# bikelight.net
KiCad netlist of a schematic drawn in Altium Designer
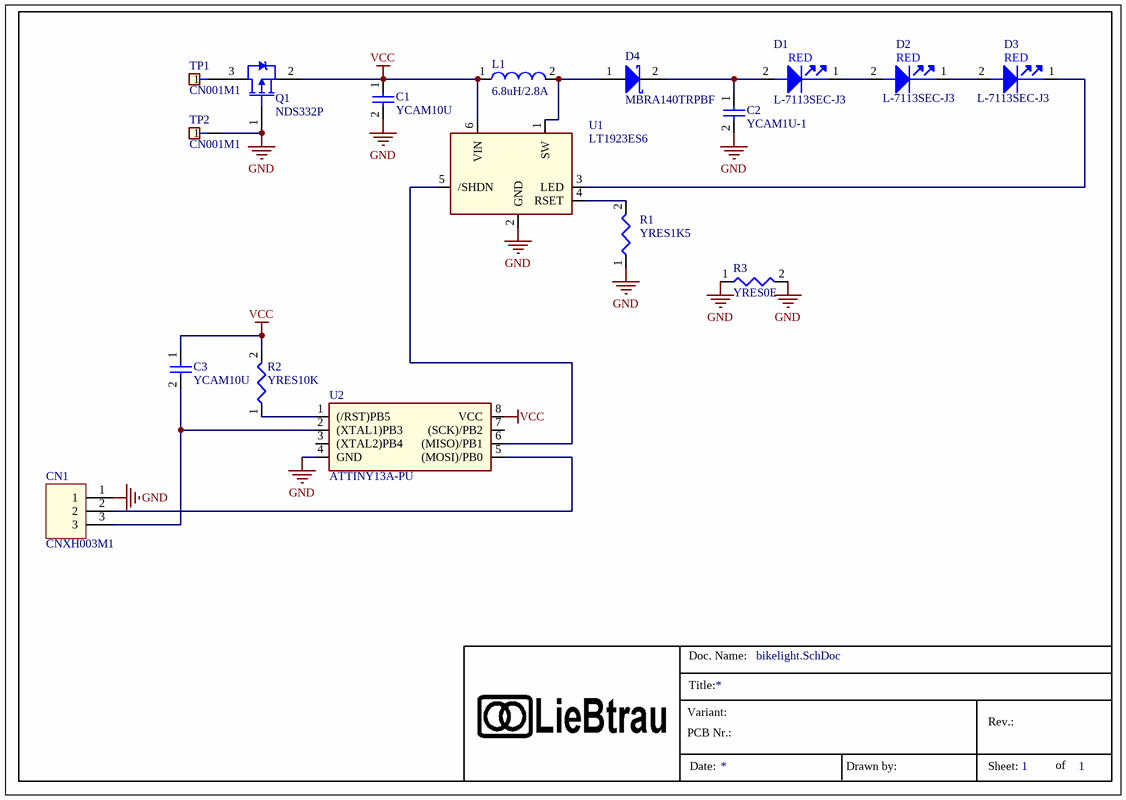
[diagram p0: bikelight.SchDoc]

(export (version "E")
  (design (tool "Eeschema 10.0.6"))
  (components
    (comp (ref "C1") (value "YCAM10U") (footprint "CA_1206") (libsource (lib "Testing") (part "CA_NONPOL")))
    (comp (ref "C2")
      (value "YCAM1U-1")
      (footprint "CA_0805")
      (fields (field (name "MANUFACTURER") "Murata"))
      (libsource (lib "Testing") (part "CA_NONPOL"))
    )
    (comp (ref "C3") (value "YCAM10U") (footprint "CA_1206") (libsource (lib "Testing") (part "CA_NONPOL")))
    (comp (ref "CN1")
      (value "CNXH003M1")
      (footprint "CN_B3B-XH-A")
      (fields (field (name "MANUFACTURER") "JST"))
      (libsource (lib "Testing") (part "CN_3P"))
    )
    (comp (ref "D1")
      (value "L-7113SEC-J3")
      (footprint "DI_LED_5MM")
      (fields (field (name "MANUFACTURER") "Kingbright"))
      (libsource (lib "Testing") (part "DI_LED_RED_2"))
    )
    (comp (ref "D2")
      (value "L-7113SEC-J3")
      (footprint "DI_LED_5MM")
      (fields (field (name "MANUFACTURER") "Kingbright"))
      (libsource (lib "Testing") (part "DI_LED_RED_2"))
    )
    (comp (ref "D3")
      (value "L-7113SEC-J3")
      (footprint "DI_LED_5MM")
      (fields (field (name "MANUFACTURER") "Kingbright"))
      (libsource (lib "Testing") (part "DI_LED_RED_2"))
    )
    (comp (ref "D4")
      (value "MBRA140TRPBF")
      (footprint "DI_DO-214AC")
      (fields (field (name "MANUFACTURER") "Vishay"))
      (libsource (lib "Testing") (part "DI_SCHOTTKY"))
    )
    (comp (ref "L1")
      (value "6.8uH/2.8A")
      (footprint "CL_VISHAY_IHLP-2525CZ-01")
      (fields (field (name "PART NUMBER") "LQH6PPN6R8M43L") (field (name "MANUFACTURER") "Murata"))
      (libsource (lib "Testing") (part "CL_COIL"))
    )
    (comp (ref "Q1")
      (value "NDS332P")
      (footprint "SC_SOT23")
      (fields (field (name "MANUFACTURER") "Fairchild Semiconductor"))
      (libsource (lib "Testing") (part "TR_PMOS"))
    )
    (comp (ref "R1")
      (value "YRES1K5")
      (footprint "RE_1206")
      (description "Resistor")
      (fields (field (name "MANUFACTURER") "Panasonic"))
      (libsource (lib "Testing") (part "RE_RES"))
    )
    (comp (ref "R2")
      (value "YRES10K")
      (footprint "RE_1206")
      (description "Resistor")
      (fields (field (name "MANUFACTURER") "Vishay Draloric"))
      (libsource (lib "Testing") (part "RE_RES"))
    )
    (comp (ref "R3")
      (value "YRES0E")
      (footprint "RE_1206")
      (description "Resistor")
      (fields (field (name "MANUFACTURER") "Vishay Draloric"))
      (libsource (lib "Testing") (part "RE_RES"))
    )
    (comp (ref "TP1")
      (value "CN001M1")
      (footprint "CN_TP_TH_1.3mm")
      (libsource (lib "Testing") (part "CN_TESTPIN"))
    )
    (comp (ref "TP2")
      (value "CN001M1")
      (footprint "CN_TP_TH_1.3mm")
      (libsource (lib "Testing") (part "CN_TESTPIN"))
    )
    (comp (ref "U1")
      (value "LT1923ES6")
      (footprint "SC_SOT23-6")
      (fields (field (name "PART NUMBER") "LT1932ES6") (field (name "MANUFACTURER") "Linear Technology"))
      (libsource (lib "Testing") (part "IC_LT1932"))
    )
    (comp (ref "U2")
      (value "ATTINY13A-PU")
      (footprint "SC_PDIP8")
      (fields (field (name "MANUFACTURER") "Atmel"))
      (libsource (lib "Testing") (part "IC_ATTINY13"))
    )
  )
  (nets
    (net (code "1") (name "GND") (class "Default")
      (node (ref "C1") (pin "2") (pinfunction "2_2") (pintype "passive"))
      (node (ref "C2") (pin "2") (pinfunction "2_2") (pintype "passive"))
      (node (ref "CN1") (pin "1") (pinfunction "1_1") (pintype "passive"))
      (node (ref "Q1") (pin "1") (pinfunction "G_1") (pintype "passive"))
      (node (ref "R1") (pin "1") (pinfunction "1_1") (pintype "passive"))
      (node (ref "R3") (pin "1") (pinfunction "1_1") (pintype "passive"))
      (node (ref "R3") (pin "2") (pinfunction "2_2") (pintype "passive"))
      (node (ref "TP2") (pin "1") (pinfunction "1_1") (pintype "passive"))
      (node (ref "U1") (pin "2") (pinfunction "GND_2") (pintype "passive"))
      (node (ref "U2") (pin "4") (pinfunction "GND_4") (pintype "passive"))
    )
    (net (code "2") (name "Net-(D1-A)") (class "Default")
      (node (ref "D1") (pin "1") (pinfunction "A_1") (pintype "passive"))
      (node (ref "D2") (pin "2") (pinfunction "C_2") (pintype "passive"))
    )
    (net (code "3") (name "Net-(D1-C)") (class "Default")
      (node (ref "C2") (pin "1") (pinfunction "1_1") (pintype "passive"))
      (node (ref "D1") (pin "2") (pinfunction "C_2") (pintype "passive"))
      (node (ref "D4") (pin "2") (pinfunction "K_2") (pintype "passive"))
    )
    (net (code "4") (name "Net-(D2-A)") (class "Default")
      (node (ref "D2") (pin "1") (pinfunction "A_1") (pintype "passive"))
      (node (ref "D3") (pin "2") (pinfunction "C_2") (pintype "passive"))
    )
    (net (code "5") (name "Net-(D3-A)") (class "Default")
      (node (ref "D3") (pin "1") (pinfunction "A_1") (pintype "passive"))
      (node (ref "U1") (pin "3") (pinfunction "LED_3") (pintype "passive"))
    )
    (net (code "6") (name "Net-(D4-A)") (class "Default")
      (node (ref "D4") (pin "1") (pinfunction "A_1") (pintype "passive"))
      (node (ref "L1") (pin "2") (pinfunction "2_2") (pintype "passive"))
      (node (ref "U1") (pin "1") (pinfunction "SW_1") (pintype "passive"))
    )
    (net (code "7") (name "Net-(Q1-D)") (class "Default")
      (node (ref "Q1") (pin "3") (pinfunction "D_3") (pintype "passive"))
      (node (ref "TP1") (pin "1") (pinfunction "1_1") (pintype "passive"))
    )
    (net (code "8") (name "Net-(U1-RSET)") (class "Default")
      (node (ref "R1") (pin "2") (pinfunction "2_2") (pintype "passive"))
      (node (ref "U1") (pin "4") (pinfunction "RSET_4") (pintype "passive"))
    )
    (net (code "9") (name "Net-(U1-{slash}SHDN)") (class "Default")
      (node (ref "U1") (pin "5") (pinfunction "/SHDN_5") (pintype "passive"))
      (node (ref "U2") (pin "6") (pinfunction "(MISO)/PB1_6") (pintype "passive"))
    )
    (net (code "10") (name "Net-(U2-(MOSI){slash}PB0)") (class "Default")
      (node (ref "CN1") (pin "2") (pinfunction "2_2") (pintype "passive"))
      (node (ref "U2") (pin "5") (pinfunction "(MOSI)/PB0_5") (pintype "passive"))
    )
    (net (code "11") (name "Net-(U2-(XTAL1)PB3)") (class "Default")
      (node (ref "C3") (pin "2") (pinfunction "2_2") (pintype "passive"))
      (node (ref "CN1") (pin "3") (pinfunction "3_3") (pintype "passive"))
      (node (ref "U2") (pin "2") (pinfunction "(XTAL1)PB3_2") (pintype "passive"))
    )
    (net (code "12") (name "Net-(U2-({slash}RST)PB5)") (class "Default")
      (node (ref "R2") (pin "1") (pinfunction "1_1") (pintype "passive"))
      (node (ref "U2") (pin "1") (pinfunction "(/RST)PB5_1") (pintype "passive"))
    )
    (net (code "13") (name "VCC") (class "Default")
      (node (ref "C1") (pin "1") (pinfunction "1_1") (pintype "passive"))
      (node (ref "C3") (pin "1") (pinfunction "1_1") (pintype "passive"))
      (node (ref "L1") (pin "1") (pinfunction "1_1") (pintype "passive"))
      (node (ref "Q1") (pin "2") (pinfunction "S_2") (pintype "passive"))
      (node (ref "R2") (pin "2") (pinfunction "2_2") (pintype "passive"))
      (node (ref "U1") (pin "6") (pinfunction "VIN_6") (pintype "passive"))
      (node (ref "U2") (pin "8") (pinfunction "VCC_8") (pintype "passive"))
    )
    (net (code "14") (name "unconnected-(U2-(SCK){slash}PB2-Pad7)") (class "Default")
      (node (ref "U2") (pin "7") (pinfunction "(SCK)/PB2_7") (pintype "passive"))
    )
    (net (code "15") (name "unconnected-(U2-(XTAL2)PB4-Pad3)") (class "Default")
      (node (ref "U2") (pin "3") (pinfunction "(XTAL2)PB4_3") (pintype "passive"))
    )
  )
)
